# boost_module.net
KiCad netlist of a schematic drawn in EAGLE
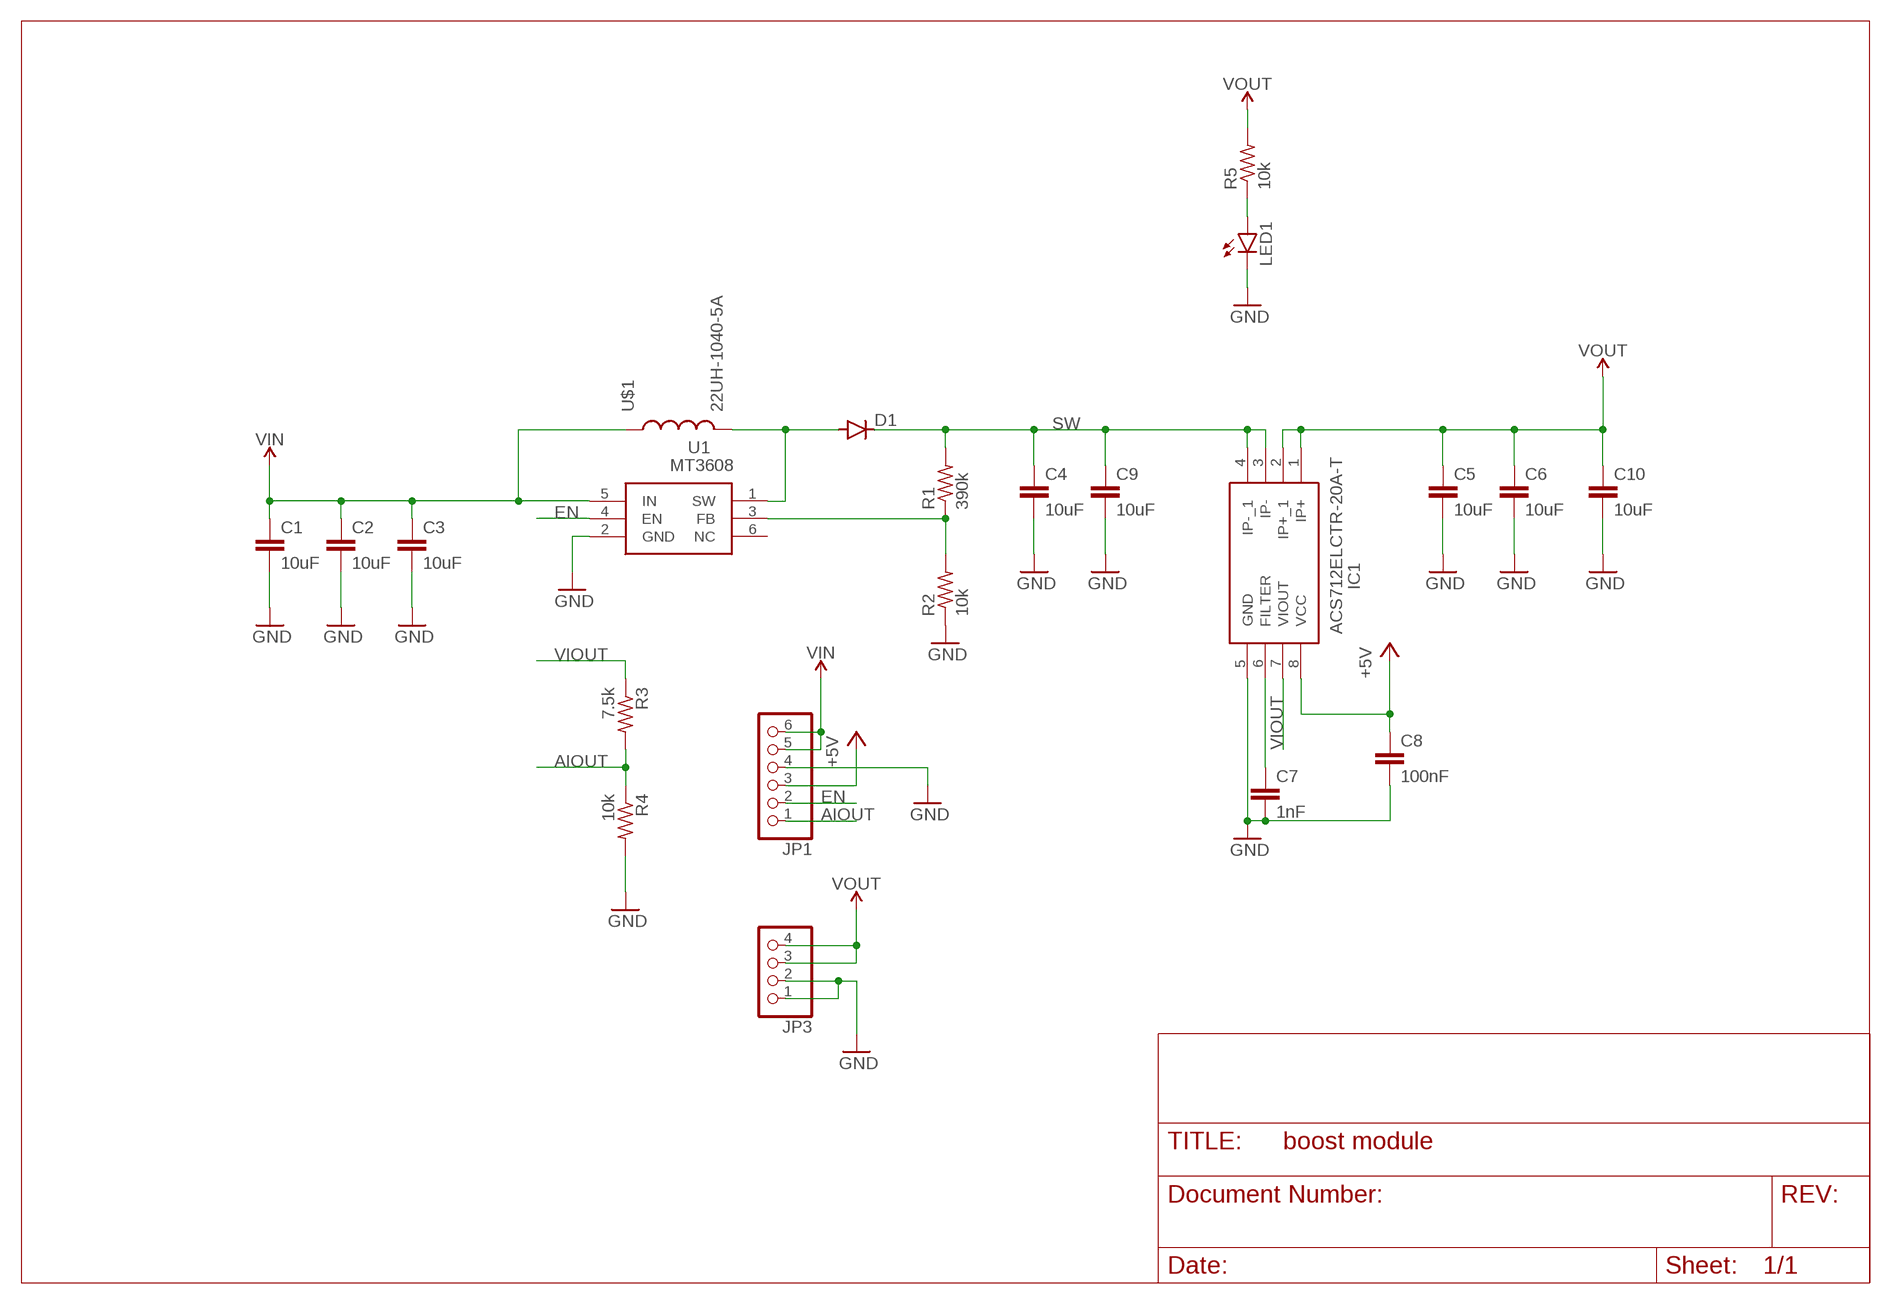
[diagram p0: schematic, sheet 1]

(export (version "E")
  (design (tool "Eeschema 10.0.6"))
  (components
    (comp (ref "C1")
      (value "10uF")
      (footprint "eagle-import:C1206")
      (libsource (lib "eagle-import") (part "C-EUC1206"))
    )
    (comp (ref "C2")
      (value "10uF")
      (footprint "eagle-import:C1206")
      (libsource (lib "eagle-import") (part "C-EUC1206"))
    )
    (comp (ref "C3")
      (value "10uF")
      (footprint "eagle-import:C1206")
      (libsource (lib "eagle-import") (part "C-EUC1206"))
    )
    (comp (ref "C4")
      (value "10uF")
      (footprint "eagle-import:C1206")
      (libsource (lib "eagle-import") (part "C-EUC1206"))
    )
    (comp (ref "C5")
      (value "10uF")
      (footprint "eagle-import:C1206")
      (libsource (lib "eagle-import") (part "C-EUC1206"))
    )
    (comp (ref "C6")
      (value "10uF")
      (footprint "eagle-import:C1206")
      (libsource (lib "eagle-import") (part "C-EUC1206"))
    )
    (comp (ref "C7")
      (value "1nF")
      (footprint "eagle-import:C0603")
      (libsource (lib "eagle-import") (part "C-EUC0603"))
    )
    (comp (ref "C8")
      (value "100nF")
      (footprint "eagle-import:C0603")
      (libsource (lib "eagle-import") (part "C-EUC0603"))
    )
    (comp (ref "C9")
      (value "10uF")
      (footprint "eagle-import:C1206")
      (libsource (lib "eagle-import") (part "C-EUC1206"))
    )
    (comp (ref "C10")
      (value "10uF")
      (footprint "eagle-import:C1206")
      (libsource (lib "eagle-import") (part "C-EUC1206"))
    )
    (comp (ref "D1")
      (value "DIODE-DO-214AC")
      (footprint "eagle-import:DO-214AC")
      (libsource (lib "eagle-import") (part "DIODE-DO-214AC"))
    )
    (comp (ref "IC1")
      (value "ACS712ELCTR-20A-T")
      (footprint "eagle-import:SOIC127P600X175-8N")
      (fields (field (name "RS_PART_NUMBER") "6807135P"))
      (libsource (lib "eagle-import") (part "ACS712ELCTR-20A-T"))
    )
    (comp (ref "JP1")
      (value "PINHD-1X6")
      (footprint "eagle-import:1X06")
      (libsource (lib "eagle-import") (part "PINHD-1X6"))
    )
    (comp (ref "JP3")
      (value "PINHD-1X4")
      (footprint "eagle-import:1X04")
      (libsource (lib "eagle-import") (part "PINHD-1X4"))
    )
    (comp (ref "LED1")
      (value "LEDCHIPLED_0805")
      (footprint "eagle-import:CHIPLED_0805")
      (libsource (lib "eagle-import") (part "LEDCHIPLED_0805"))
    )
    (comp (ref "R1")
      (value "390k")
      (footprint "eagle-import:R0603")
      (libsource (lib "eagle-import") (part "R-US_R0603"))
    )
    (comp (ref "R2")
      (value "10k")
      (footprint "eagle-import:R0603")
      (libsource (lib "eagle-import") (part "R-US_R0603"))
    )
    (comp (ref "R3")
      (value "7.5k")
      (footprint "eagle-import:R0603")
      (libsource (lib "eagle-import") (part "R-US_R0603"))
    )
    (comp (ref "R4")
      (value "10k")
      (footprint "eagle-import:R0603")
      (libsource (lib "eagle-import") (part "R-US_R0603"))
    )
    (comp (ref "R5")
      (value "10k")
      (footprint "eagle-import:R0603")
      (libsource (lib "eagle-import") (part "R-US_R0603"))
    )
    (comp (ref "U$1")
      (value "22UH-1040-5A")
      (footprint "eagle-import:22UH-1040-5A")
      (libsource (lib "eagle-import") (part "22UH-1040-5A"))
    )
    (comp (ref "U1")
      (value "MT3608")
      (footprint "eagle-import:SOT95P280X145-6N")
      (libsource (lib "eagle-import") (part "MT3608"))
    )
  )
  (nets
    (net (code "1") (name "+5V") (class "Default")
      (node (ref "C8") (pin "1") (pinfunction "1_1") (pintype "passive"))
      (node (ref "IC1") (pin "8") (pinfunction "VCC_8") (pintype "power_in"))
      (node (ref "JP1") (pin "3") (pinfunction "3_3") (pintype "passive"))
    )
    (net (code "2") (name "/AIOUT") (class "Default")
      (node (ref "JP1") (pin "1") (pinfunction "1_1") (pintype "passive"))
      (node (ref "R3") (pin "2") (pinfunction "2_2") (pintype "passive"))
      (node (ref "R4") (pin "1") (pinfunction "1_1") (pintype "passive"))
    )
    (net (code "3") (name "/EN") (class "Default")
      (node (ref "JP1") (pin "2") (pinfunction "2_2") (pintype "passive"))
      (node (ref "U1") (pin "4") (pinfunction "EN_4") (pintype "bidirectional"))
    )
    (net (code "4") (name "/SW") (class "Default")
      (node (ref "C4") (pin "1") (pinfunction "1_1") (pintype "passive"))
      (node (ref "C9") (pin "1") (pinfunction "1_1") (pintype "passive"))
      (node (ref "D1") (pin "C") (pinfunction "C_C") (pintype "passive"))
      (node (ref "IC1") (pin "3") (pinfunction "IP-_3") (pintype "bidirectional"))
      (node (ref "IC1") (pin "4") (pinfunction "IP-_1_4") (pintype "bidirectional"))
      (node (ref "R1") (pin "2") (pinfunction "2_2") (pintype "passive"))
    )
    (net (code "5") (name "/VIOUT") (class "Default")
      (node (ref "IC1") (pin "7") (pinfunction "VIOUT_7") (pintype "bidirectional"))
      (node (ref "R3") (pin "1") (pinfunction "1_1") (pintype "passive"))
    )
    (net (code "6") (name "GND") (class "Default")
      (node (ref "C1") (pin "2") (pinfunction "2_2") (pintype "passive"))
      (node (ref "C10") (pin "2") (pinfunction "2_2") (pintype "passive"))
      (node (ref "C2") (pin "2") (pinfunction "2_2") (pintype "passive"))
      (node (ref "C3") (pin "2") (pinfunction "2_2") (pintype "passive"))
      (node (ref "C4") (pin "2") (pinfunction "2_2") (pintype "passive"))
      (node (ref "C5") (pin "2") (pinfunction "2_2") (pintype "passive"))
      (node (ref "C6") (pin "2") (pinfunction "2_2") (pintype "passive"))
      (node (ref "C7") (pin "2") (pinfunction "2_2") (pintype "passive"))
      (node (ref "C8") (pin "2") (pinfunction "2_2") (pintype "passive"))
      (node (ref "C9") (pin "2") (pinfunction "2_2") (pintype "passive"))
      (node (ref "IC1") (pin "5") (pinfunction "GND_5") (pintype "power_in"))
      (node (ref "JP1") (pin "4") (pinfunction "4_4") (pintype "passive"))
      (node (ref "JP3") (pin "1") (pinfunction "1_1") (pintype "passive"))
      (node (ref "JP3") (pin "2") (pinfunction "2_2") (pintype "passive"))
      (node (ref "LED1") (pin "C") (pinfunction "C_C") (pintype "passive"))
      (node (ref "R2") (pin "1") (pinfunction "1_1") (pintype "passive"))
      (node (ref "R4") (pin "2") (pinfunction "2_2") (pintype "passive"))
      (node (ref "U1") (pin "2") (pinfunction "GND_2") (pintype "bidirectional"))
    )
    (net (code "7") (name "Net-(IC1-FILTER)") (class "Default")
      (node (ref "C7") (pin "1") (pinfunction "1_1") (pintype "passive"))
      (node (ref "IC1") (pin "6") (pinfunction "FILTER_6") (pintype "bidirectional"))
    )
    (net (code "8") (name "Net-(LED1-PadA)") (class "Default")
      (node (ref "LED1") (pin "A") (pinfunction "A_A") (pintype "passive"))
      (node (ref "R5") (pin "1") (pinfunction "1_1") (pintype "passive"))
    )
    (net (code "9") (name "Net-(U$1-2)") (class "Default")
      (node (ref "D1") (pin "A") (pinfunction "A_A") (pintype "passive"))
      (node (ref "U$1") (pin "P$2") (pinfunction "2_P$2") (pintype "passive"))
      (node (ref "U1") (pin "1") (pinfunction "SW_1") (pintype "bidirectional"))
    )
    (net (code "10") (name "Net-(U1-FB)") (class "Default")
      (node (ref "R1") (pin "1") (pinfunction "1_1") (pintype "passive"))
      (node (ref "R2") (pin "2") (pinfunction "2_2") (pintype "passive"))
      (node (ref "U1") (pin "3") (pinfunction "FB_3") (pintype "bidirectional"))
    )
    (net (code "11") (name "VIN") (class "Default")
      (node (ref "C1") (pin "1") (pinfunction "1_1") (pintype "passive"))
      (node (ref "C2") (pin "1") (pinfunction "1_1") (pintype "passive"))
      (node (ref "C3") (pin "1") (pinfunction "1_1") (pintype "passive"))
      (node (ref "JP1") (pin "5") (pinfunction "5_5") (pintype "passive"))
      (node (ref "JP1") (pin "6") (pinfunction "6_6") (pintype "passive"))
      (node (ref "U$1") (pin "P$1") (pinfunction "1_P$1") (pintype "passive"))
      (node (ref "U1") (pin "5") (pinfunction "IN_5") (pintype "bidirectional"))
    )
    (net (code "12") (name "VOUT") (class "Default")
      (node (ref "C10") (pin "1") (pinfunction "1_1") (pintype "passive"))
      (node (ref "C5") (pin "1") (pinfunction "1_1") (pintype "passive"))
      (node (ref "C6") (pin "1") (pinfunction "1_1") (pintype "passive"))
      (node (ref "IC1") (pin "1") (pinfunction "IP+_1") (pintype "bidirectional"))
      (node (ref "IC1") (pin "2") (pinfunction "IP+_1_2") (pintype "bidirectional"))
      (node (ref "JP3") (pin "3") (pinfunction "3_3") (pintype "passive"))
      (node (ref "JP3") (pin "4") (pinfunction "4_4") (pintype "passive"))
      (node (ref "R5") (pin "2") (pinfunction "2_2") (pintype "passive"))
    )
    (net (code "13") (name "unconnected-(U1-NC-Pad6)") (class "Default")
      (node (ref "U1") (pin "6") (pinfunction "NC_6") (pintype "no_connect"))
    )
  )
)
